# Processor_Interface.net
KiCad netlist of a schematic drawn in Altium Designer
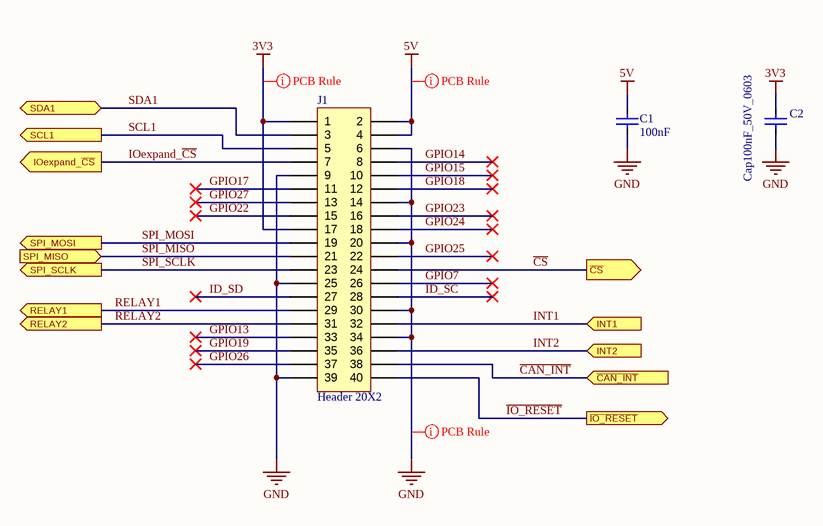
[diagram p0: Processor_Interface.SchDoc]

(export (version "E")
  (design (tool "Eeschema 10.0.6"))
  (components
    (comp (ref "C1")
      (value "100nF")
      (footprint "0603C_L")
      (fields (field (name "Comment") "Cap100nF_50V_0603"))
      (libsource (lib "TC - Altium Essentials Course A365 13") (part "CAP General"))
    )
    (comp (ref "C2")
      (value "Cap100nF_50V_0603")
      (footprint "0603C_L")
      (libsource (lib "Advanced] Training Course - A365") (part "CAP General"))
    )
    (comp (ref "J1")
      (value "Header 20X2")
      (footprint "HDR2X20")
      (description "Header, 20-Pin, Dual row")
      (fields (field (name "PUBLISHER") "Altium Limited"))
      (libsource (lib "Advanced] Training Course - A365") (part "Header 20X2"))
    )
  )
  (nets
    (net (code "1") (name "/CAN_INT") (class "Default")
      (node (ref "J1") (pin "38") (pinfunction "38_38") (pintype "passive"))
    )
    (net (code "2") (name "/GPIO7") (class "Default")
      (node (ref "J1") (pin "26") (pinfunction "26_26") (pintype "passive+no_connect"))
    )
    (net (code "3") (name "/GPIO13") (class "Default")
      (node (ref "J1") (pin "33") (pinfunction "33_33") (pintype "passive+no_connect"))
    )
    (net (code "4") (name "/GPIO14") (class "Default")
      (node (ref "J1") (pin "8") (pinfunction "8_8") (pintype "passive+no_connect"))
    )
    (net (code "5") (name "/GPIO15") (class "Default")
      (node (ref "J1") (pin "10") (pinfunction "10_10") (pintype "passive+no_connect"))
    )
    (net (code "6") (name "/GPIO17") (class "Default")
      (node (ref "J1") (pin "11") (pinfunction "11_11") (pintype "passive+no_connect"))
    )
    (net (code "7") (name "/GPIO18") (class "Default")
      (node (ref "J1") (pin "12") (pinfunction "12_12") (pintype "passive+no_connect"))
    )
    (net (code "8") (name "/GPIO19") (class "Default")
      (node (ref "J1") (pin "35") (pinfunction "35_35") (pintype "passive+no_connect"))
    )
    (net (code "9") (name "/GPIO22") (class "Default")
      (node (ref "J1") (pin "15") (pinfunction "15_15") (pintype "passive+no_connect"))
    )
    (net (code "10") (name "/GPIO23") (class "Default")
      (node (ref "J1") (pin "16") (pinfunction "16_16") (pintype "passive+no_connect"))
    )
    (net (code "11") (name "/GPIO24") (class "Default")
      (node (ref "J1") (pin "18") (pinfunction "18_18") (pintype "passive+no_connect"))
    )
    (net (code "12") (name "/GPIO25") (class "Default")
      (node (ref "J1") (pin "22") (pinfunction "22_22") (pintype "passive+no_connect"))
    )
    (net (code "13") (name "/GPIO26") (class "Default")
      (node (ref "J1") (pin "37") (pinfunction "37_37") (pintype "passive+no_connect"))
    )
    (net (code "14") (name "/GPIO27") (class "Default")
      (node (ref "J1") (pin "13") (pinfunction "13_13") (pintype "passive+no_connect"))
    )
    (net (code "15") (name "/ID_SC") (class "Default")
      (node (ref "J1") (pin "28") (pinfunction "28_28") (pintype "passive+no_connect"))
    )
    (net (code "16") (name "/ID_SD") (class "Default")
      (node (ref "J1") (pin "27") (pinfunction "27_27") (pintype "passive+no_connect"))
    )
    (net (code "17") (name "/INT1") (class "Default")
      (node (ref "J1") (pin "32") (pinfunction "32_32") (pintype "passive"))
    )
    (net (code "18") (name "/INT2") (class "Default")
      (node (ref "J1") (pin "36") (pinfunction "36_36") (pintype "passive"))
    )
    (net (code "19") (name "/IO_RESET") (class "Default")
      (node (ref "J1") (pin "40") (pinfunction "40_40") (pintype "passive"))
    )
    (net (code "20") (name "/IOexpand_~{CS}") (class "Default")
      (node (ref "J1") (pin "7") (pinfunction "7_7") (pintype "passive"))
    )
    (net (code "21") (name "/RELAY1") (class "Default")
      (node (ref "J1") (pin "29") (pinfunction "29_29") (pintype "passive"))
    )
    (net (code "22") (name "/RELAY2") (class "Default")
      (node (ref "J1") (pin "31") (pinfunction "31_31") (pintype "passive"))
    )
    (net (code "23") (name "/SCL1") (class "Default")
      (node (ref "J1") (pin "5") (pinfunction "5_5") (pintype "passive"))
    )
    (net (code "24") (name "/SDA1") (class "Default")
      (node (ref "J1") (pin "3") (pinfunction "3_3") (pintype "passive"))
    )
    (net (code "25") (name "/SPI_MISO") (class "Default")
      (node (ref "J1") (pin "21") (pinfunction "21_21") (pintype "passive"))
    )
    (net (code "26") (name "/SPI_MOSI") (class "Default")
      (node (ref "J1") (pin "19") (pinfunction "19_19") (pintype "passive"))
    )
    (net (code "27") (name "/SPI_SCLK") (class "Default")
      (node (ref "J1") (pin "23") (pinfunction "23_23") (pintype "passive"))
    )
    (net (code "28") (name "/~{CS}") (class "Default")
      (node (ref "J1") (pin "24") (pinfunction "24_24") (pintype "passive"))
    )
    (net (code "29") (name "3V3") (class "Default")
      (node (ref "C2") (pin "2") (pinfunction "2_2") (pintype "passive"))
      (node (ref "J1") (pin "1") (pinfunction "1_1") (pintype "passive"))
      (node (ref "J1") (pin "17") (pinfunction "17_17") (pintype "passive"))
    )
    (net (code "30") (name "5V") (class "Default")
      (node (ref "C1") (pin "2") (pinfunction "2_2") (pintype "passive"))
      (node (ref "J1") (pin "2") (pinfunction "2_2") (pintype "passive"))
      (node (ref "J1") (pin "4") (pinfunction "4_4") (pintype "passive"))
    )
    (net (code "31") (name "GND") (class "Default")
      (node (ref "C1") (pin "1") (pinfunction "1_1") (pintype "passive"))
      (node (ref "C2") (pin "1") (pinfunction "1_1") (pintype "passive"))
      (node (ref "J1") (pin "14") (pinfunction "14_14") (pintype "passive"))
      (node (ref "J1") (pin "20") (pinfunction "20_20") (pintype "passive"))
      (node (ref "J1") (pin "25") (pinfunction "25_25") (pintype "passive"))
      (node (ref "J1") (pin "30") (pinfunction "30_30") (pintype "passive"))
      (node (ref "J1") (pin "34") (pinfunction "34_34") (pintype "passive"))
      (node (ref "J1") (pin "39") (pinfunction "39_39") (pintype "passive"))
      (node (ref "J1") (pin "6") (pinfunction "6_6") (pintype "passive"))
      (node (ref "J1") (pin "9") (pinfunction "9_9") (pintype "passive"))
    )
  )
)
